# design.net
KiCad netlist of a schematic drawn in EasyEDA Pro
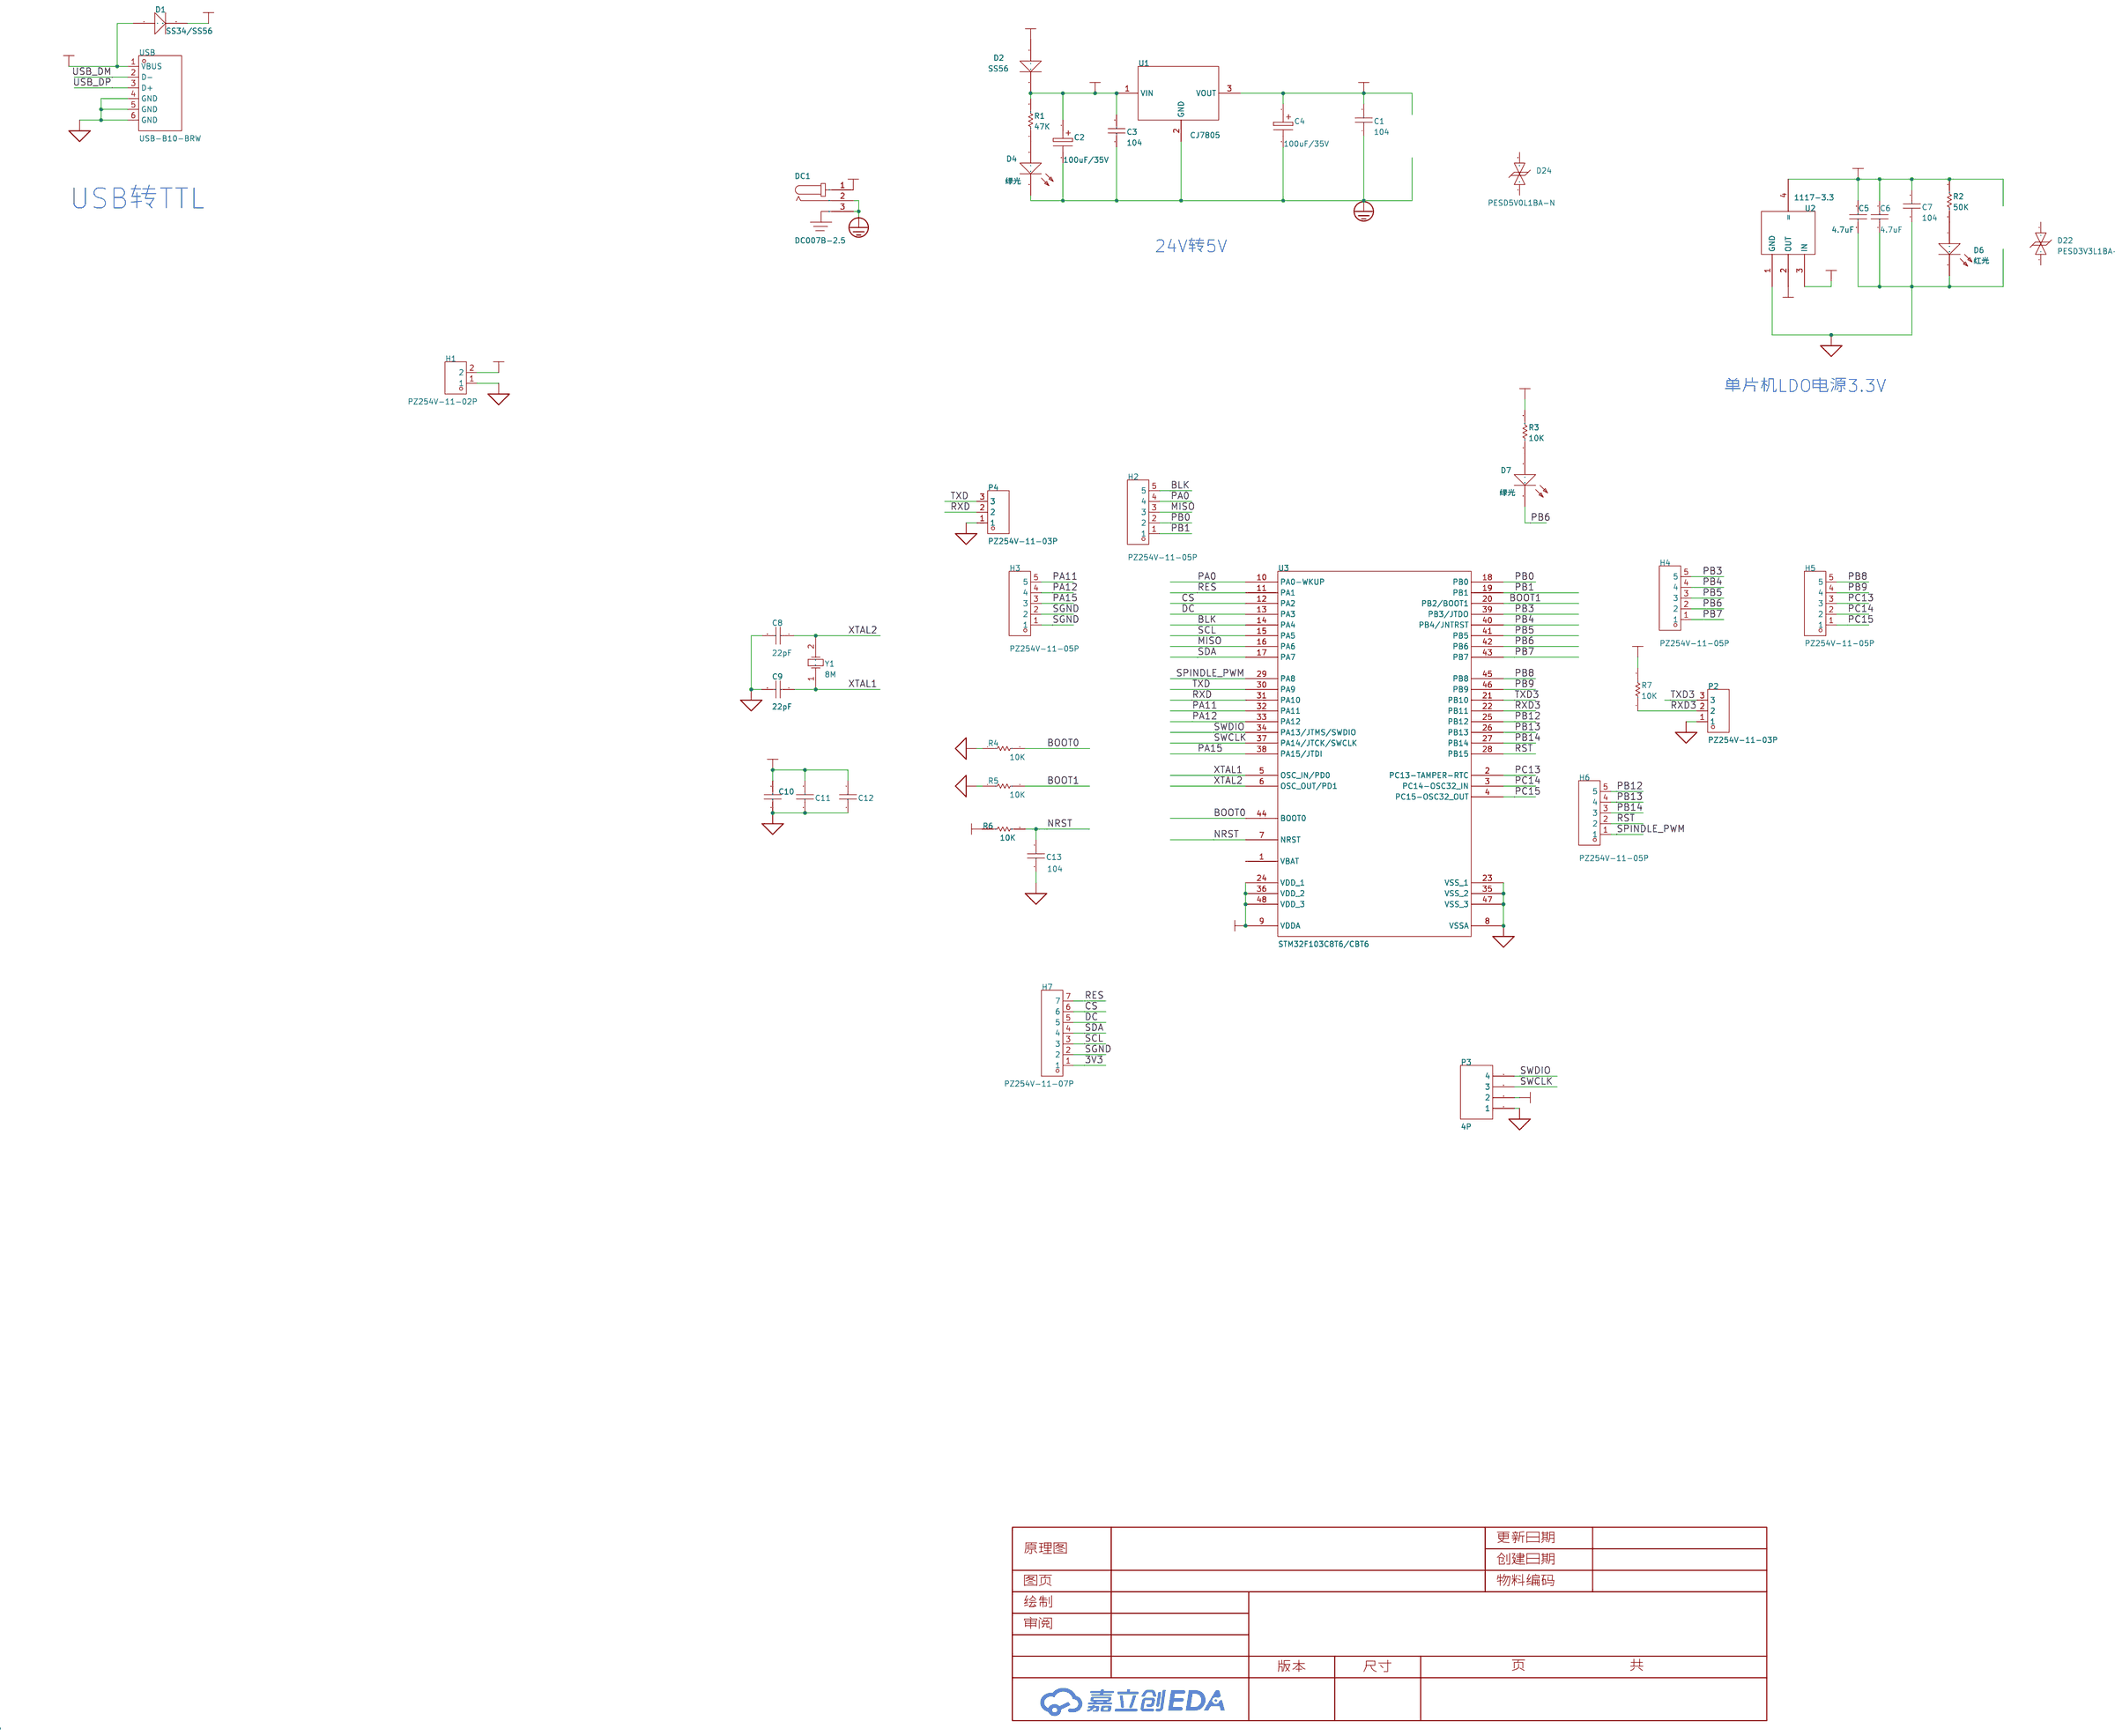
[diagram p0: 主控MCU]
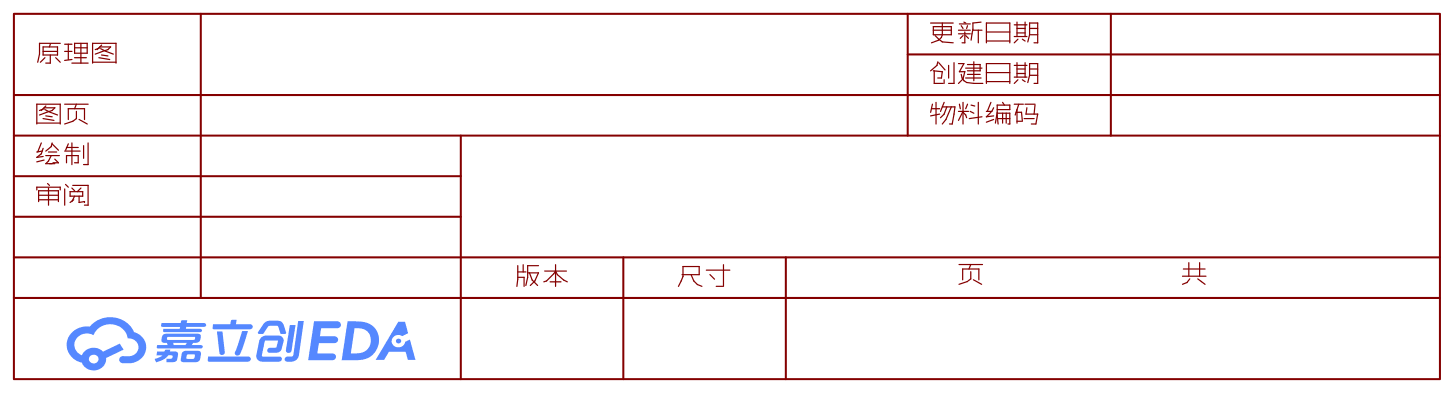
[diagram p1: 电源及控制]

(export (version "E")
  (design (tool "Eeschema 10.0.6"))
  (components
    (comp (ref "C1")
      (value "104")
      (footprint "easyedapro:0603C")
      (description "Capacitor (Semiconductor SIM Model)")
      (libsource (lib "easyedapro") (part "Cap Semi"))
    )
    (comp (ref "C2")
      (value "100uF/35V")
      (footprint "easyedapro:0603C")
      (libsource (lib "easyedapro") (part "ELECTRO1"))
    )
    (comp (ref "C3")
      (value "104")
      (footprint "easyedapro:0603C")
      (description "Capacitor (Semiconductor SIM Model)")
      (libsource (lib "easyedapro") (part "Cap Semi"))
    )
    (comp (ref "C4")
      (value "100uF/35V")
      (footprint "easyedapro:0603C")
      (libsource (lib "easyedapro") (part "ELECTRO1"))
    )
    (comp (ref "C5") (value "4.7uF") (libsource (lib "") (part "CAP_1")))
    (comp (ref "C6") (value "4.7uF") (libsource (lib "") (part "CAP_1")))
    (comp (ref "C7")
      (value "104")
      (footprint "easyedapro:0603C")
      (description "Capacitor (Semiconductor SIM Model)")
      (libsource (lib "easyedapro") (part "Cap Semi"))
    )
    (comp (ref "C8")
      (value "100pF")
      (footprint "easyedapro:0603C")
      (description "Capacitor (Semiconductor SIM Model)")
      (libsource (lib "easyedapro") (part "Cap Semi"))
    )
    (comp (ref "C9")
      (value "100pF")
      (footprint "easyedapro:0603C")
      (description "Capacitor (Semiconductor SIM Model)")
      (libsource (lib "easyedapro") (part "Cap Semi"))
    )
    (comp (ref "C10")
      (value "104")
      (footprint "easyedapro:电解电容贴片6X6")
      (libsource (lib "easyedapro") (part "CAP"))
    )
    (comp (ref "C11")
      (value "104")
      (footprint "easyedapro:电解电容贴片6X6")
      (libsource (lib "easyedapro") (part "CAP"))
    )
    (comp (ref "C12")
      (value "104")
      (footprint "easyedapro:电解电容贴片6X6")
      (libsource (lib "easyedapro") (part "CAP"))
    )
    (comp (ref "C13")
      (value "104")
      (footprint "easyedapro:0603C")
      (description "Capacitor (Semiconductor SIM Model)")
      (libsource (lib "easyedapro") (part "Cap Semi"))
    )
    (comp (ref "D1")
      (value "SS34/SS56")
      (footprint "easyedapro:SMA")
      (libsource (lib "easyedapro") (part "1N4148"))
    )
    (comp (ref "D2")
      (value "SS56")
      (footprint "easyedapro:SMA")
      (libsource (lib "easyedapro") (part "1N4148"))
    )
    (comp (ref "D4")
      (value "绿光")
      (footprint "easyedapro:0603LED")
      (libsource (lib "easyedapro") (part "LED"))
    )
    (comp (ref "D6")
      (value "红光")
      (footprint "easyedapro:0603LED")
      (libsource (lib "easyedapro") (part "LED"))
    )
    (comp (ref "D7")
      (value "绿光")
      (footprint "easyedapro:0603LED")
      (libsource (lib "easyedapro") (part "LED"))
    )
    (comp (ref "D22")
      (value "PESD3V3L1BA-N")
      (footprint "easyedapro:SOD-523_L1.2-W0.8-LS1.6-BI")
      (description "极性:Bidirectional;反向关断电压（典型值）:5V (Max);击穿电压（最小值）:6V;箝位电压:15V;峰值脉冲电流（10/1000us）:5A (8/20us);")
      (fields (field (name "Manufacturer") "BORN伯恩半导体"))
      (libsource (lib "easyedapro") (part "PESD5V0S1BBN"))
    )
    (comp (ref "D24")
      (value "PESD5V0L1BA-N")
      (footprint "easyedapro:SOD-523_L1.2-W0.8-LS1.6-BI")
      (description "极性:Bidirectional;反向关断电压（典型值）:5V (Max);击穿电压（最小值）:6V;箝位电压:15V;峰值脉冲电流（10/1000us）:5A (8/20us);")
      (fields (field (name "Manufacturer") "BORN伯恩半导体"))
      (libsource (lib "easyedapro") (part "PESD5V0S1BBN"))
    )
    (comp (ref "DC1")
      (value "DC007B-2.5")
      (footprint "easyedapro:DC-IN-TH_HX-DC007B-2.5")
      (description "连接器类型:DC电源插座;安装方式:弯插;触点内径:2.5mm;触点外径:7.7mm;额定电流:5A;额定电压:20V;工作温度:-25°C~+70°C;")
      (fields (field (name "Manufacturer") "SHOU HAN(首韩)"))
      (libsource (lib "easyedapro") (part "DC007B-2.5"))
    )
    (comp (ref "H1")
      (value "PZ254V-11-02P")
      (footprint "easyedapro:HDR-TH_2P-P2.54-V-M")
      (fields (field (name "Manufacturer") "XFCN(兴飞)"))
      (libsource (lib "easyedapro") (part "PZ254V-11-02P"))
    )
    (comp (ref "H2")
      (value "PZ254V-11-05P")
      (footprint "easyedapro:HDR-TH_5P-P2.54-V-M")
      (fields (field (name "Manufacturer") "XFCN(兴飞)"))
      (libsource (lib "easyedapro") (part "PZ254V-11-05P"))
    )
    (comp (ref "H3")
      (value "PZ254V-11-05P")
      (footprint "easyedapro:HDR-TH_5P-P2.54-V-M")
      (fields (field (name "Manufacturer") "XFCN(兴飞)"))
      (libsource (lib "easyedapro") (part "PZ254V-11-05P"))
    )
    (comp (ref "H4")
      (value "PZ254V-11-05P")
      (footprint "easyedapro:HDR-TH_5P-P2.54-V-M")
      (fields (field (name "Manufacturer") "XFCN(兴飞)"))
      (libsource (lib "easyedapro") (part "PZ254V-11-05P"))
    )
    (comp (ref "H5")
      (value "PZ254V-11-05P")
      (footprint "easyedapro:HDR-TH_5P-P2.54-V-M")
      (fields (field (name "Manufacturer") "XFCN(兴飞)"))
      (libsource (lib "easyedapro") (part "PZ254V-11-05P"))
    )
    (comp (ref "H6")
      (value "PZ254V-11-05P")
      (footprint "easyedapro:HDR-TH_5P-P2.54-V-M")
      (fields (field (name "Manufacturer") "XFCN(兴飞)"))
      (libsource (lib "easyedapro") (part "PZ254V-11-05P"))
    )
    (comp (ref "H7")
      (value "PZ254V-11-07P")
      (footprint "easyedapro:HDR-TH_7P-P2.54-V-M")
      (fields (field (name "Manufacturer") "XFCN(兴飞)"))
      (libsource (lib "easyedapro") (part "PZ254V-11-07P"))
    )
    (comp (ref "P2")
      (value "PZ254V-11-03P")
      (footprint "easyedapro:HDR-TH_3P-P2.54-V-M")
      (fields (field (name "Manufacturer") "XFCN(兴飞)"))
      (libsource (lib "easyedapro") (part "PZ254V-11-03P_C2937625"))
    )
    (comp (ref "P3") (value "4P") (libsource (lib "easyedapro") (part "4P")))
    (comp (ref "P4")
      (value "PZ254V-11-03P")
      (footprint "easyedapro:HDR-TH_3P-P2.54-V-M")
      (fields (field (name "Manufacturer") "XFCN(兴飞)"))
      (libsource (lib "easyedapro") (part "PZ254V-11-03P_C2937625"))
    )
    (comp (ref "R1")
      (value "47K")
      (footprint "easyedapro:0603R")
      (description "Resistor")
      (libsource (lib "easyedapro") (part "RES"))
    )
    (comp (ref "R2")
      (value "50K")
      (footprint "easyedapro:0603R")
      (description "Resistor")
      (libsource (lib "easyedapro") (part "RES"))
    )
    (comp (ref "R3")
      (value "10K")
      (footprint "easyedapro:0603R")
      (description "Resistor")
      (libsource (lib "easyedapro") (part "RES"))
    )
    (comp (ref "R4")
      (value "10K")
      (footprint "easyedapro:0603R")
      (description "Resistor")
      (libsource (lib "easyedapro") (part "RES"))
    )
    (comp (ref "R5")
      (value "10K")
      (footprint "easyedapro:0603R")
      (description "Resistor")
      (libsource (lib "easyedapro") (part "RES"))
    )
    (comp (ref "R6")
      (value "10K")
      (footprint "easyedapro:0603R")
      (description "Resistor")
      (libsource (lib "easyedapro") (part "RES"))
    )
    (comp (ref "R7")
      (value "10K")
      (footprint "easyedapro:0603R")
      (description "Resistor")
      (libsource (lib "easyedapro") (part "RES"))
    )
    (comp (ref "U1")
      (value "CJ7805")
      (footprint "easyedapro:TO-263-2")
      (libsource (lib "easyedapro") (part "7805"))
    )
    (comp (ref "U2")
      (value "1117-3.3")
      (footprint "easyedapro:SOT-223")
      (libsource (lib "easyedapro") (part "LM1117"))
    )
    (comp (ref "U3")
      (value "STM32F103C8T6/CBT6")
      (footprint "easyedapro:LQFP48")
      (description "STM32 ARM-based 32-bit MCU with 32 Kbytes Flash, 48-pin LQFP, Industrial Temperature")
      (libsource (lib "easyedapro") (part "STM32F103C6T6"))
    )
    (comp (ref "USB")
      (value "USB-B10-BRW")
      (footprint "easyedapro:USB-B-TH_USB-B10-BRW")
      (fields (field (name "Manufacturer") "XUNPU(讯普)"))
      (libsource (lib "easyedapro") (part "USB-B10-BRW"))
    )
    (comp (ref "Y1")
      (value "8M")
      (footprint "easyedapro:晶振贴片49SSMD")
      (description "Crystal Oscillator")
      (libsource (lib "easyedapro") (part "XTAL"))
    )
  )
  (nets
    (net (code "1") (name "3V3") (class "Default")
      (node (ref "C10") (pin "2") (pinfunction "2_2") (pintype "unspecified"))
      (node (ref "C11") (pin "2") (pinfunction "2_2") (pintype "unspecified"))
      (node (ref "C12") (pin "2") (pinfunction "2_2") (pintype "unspecified"))
      (node (ref "C5") (pin "2") (pinfunction "2_2") (pintype "input"))
      (node (ref "C6") (pin "2") (pinfunction "2_2") (pintype "input"))
      (node (ref "C7") (pin "2") (pinfunction "2_2") (pintype "unspecified"))
      (node (ref "H7") (pin "1") (pinfunction "1_1") (pintype "unspecified"))
      (node (ref "P3") (pin "2") (pinfunction "2_2") (pintype "input"))
      (node (ref "R2") (pin "1") (pinfunction "1_1") (pintype "unspecified"))
      (node (ref "R3") (pin "2") (pinfunction "2_2") (pintype "unspecified"))
      (node (ref "R6") (pin "1") (pinfunction "1_1") (pintype "unspecified"))
      (node (ref "R7") (pin "2") (pinfunction "2_2") (pintype "unspecified"))
      (node (ref "U2") (pin "2") (pinfunction "OUT_2") (pintype "unspecified"))
      (node (ref "U2") (pin "4") (pinfunction "=_4") (pintype "unspecified"))
      (node (ref "U3") (pin "24") (pinfunction "VDD_1_24") (pintype "unspecified"))
      (node (ref "U3") (pin "36") (pinfunction "VDD_2_36") (pintype "unspecified"))
      (node (ref "U3") (pin "48") (pinfunction "VDD_3_48") (pintype "unspecified"))
      (node (ref "U3") (pin "9") (pinfunction "VDDA_9") (pintype "unspecified"))
    )
    (net (code "2") (name "5V_VCC") (class "Default")
      (node (ref "C1") (pin "2") (pinfunction "2_2") (pintype "unspecified"))
      (node (ref "C4") (pin "1") (pintype "unspecified"))
      (node (ref "D1") (pin "2") (pinfunction "2_2") (pintype "unspecified"))
      (node (ref "H1") (pin "2") (pinfunction "2_2") (pintype "unspecified"))
      (node (ref "U1") (pin "3") (pinfunction "VOUT_3") (pintype "unspecified"))
      (node (ref "U2") (pin "3") (pinfunction "IN_3") (pintype "unspecified"))
    )
    (net (code "3") (name "24V") (class "Default")
      (node (ref "D2") (pin "1") (pinfunction "1_1") (pintype "unspecified"))
      (node (ref "DC1") (pin "1") (pinfunction "1_1") (pintype "unspecified"))
    )
    (net (code "4") (name "BLK") (class "Default")
      (node (ref "H2") (pin "5") (pinfunction "5_5") (pintype "input"))
      (node (ref "U3") (pin "14") (pinfunction "PA4_14") (pintype "bidirectional"))
    )
    (net (code "5") (name "BOOT0") (class "Default")
      (node (ref "R4") (pin "2") (pinfunction "2_2") (pintype "unspecified"))
      (node (ref "U3") (pin "44") (pinfunction "BOOT0_44") (pintype "input"))
    )
    (net (code "6") (name "BOOT1") (class "Default")
      (node (ref "R5") (pin "2") (pinfunction "2_2") (pintype "unspecified"))
      (node (ref "U3") (pin "20") (pinfunction "PB2/BOOT1_20") (pintype "bidirectional"))
    )
    (net (code "7") (name "CS") (class "Default")
      (node (ref "H7") (pin "6") (pinfunction "6_6") (pintype "unspecified"))
      (node (ref "U3") (pin "12") (pinfunction "PA2_12") (pintype "bidirectional"))
    )
    (net (code "8") (name "DC") (class "Default")
      (node (ref "H7") (pin "5") (pinfunction "5_5") (pintype "unspecified"))
      (node (ref "U3") (pin "13") (pinfunction "PA3_13") (pintype "bidirectional"))
    )
    (net (code "9") (name "MISO") (class "Default")
      (node (ref "H2") (pin "3") (pinfunction "3_3") (pintype "input"))
      (node (ref "U3") (pin "16") (pinfunction "PA6_16") (pintype "bidirectional"))
    )
    (net (code "10") (name "NRST") (class "Default")
      (node (ref "C13") (pin "2") (pinfunction "2_2") (pintype "unspecified"))
      (node (ref "R6") (pin "2") (pinfunction "2_2") (pintype "unspecified"))
      (node (ref "U3") (pin "7") (pinfunction "NRST_7") (pintype "bidirectional"))
    )
    (net (code "11") (name "Net-(D4-Pad1)") (class "Default")
      (node (ref "D4") (pin "1") (pinfunction "1_1") (pintype "unspecified"))
      (node (ref "R1") (pin "1") (pinfunction "1_1") (pintype "unspecified"))
    )
    (net (code "12") (name "Net-(D6-Pad1)") (class "Default")
      (node (ref "D6") (pin "1") (pinfunction "1_1") (pintype "unspecified"))
      (node (ref "R2") (pin "2") (pinfunction "2_2") (pintype "unspecified"))
    )
    (net (code "13") (name "Net-(D7-Pad1)") (class "Default")
      (node (ref "D7") (pin "1") (pinfunction "1_1") (pintype "unspecified"))
      (node (ref "R3") (pin "1") (pinfunction "1_1") (pintype "unspecified"))
    )
    (net (code "14") (name "PA0") (class "Default")
      (node (ref "H2") (pin "4") (pinfunction "4_4") (pintype "input"))
      (node (ref "U3") (pin "10") (pinfunction "PA0-WKUP_10") (pintype "bidirectional"))
    )
    (net (code "15") (name "PA11") (class "Default")
      (node (ref "H3") (pin "5") (pinfunction "5_5") (pintype "input"))
      (node (ref "U3") (pin "32") (pinfunction "PA11_32") (pintype "bidirectional"))
    )
    (net (code "16") (name "PA12") (class "Default")
      (node (ref "H3") (pin "4") (pinfunction "4_4") (pintype "input"))
      (node (ref "U3") (pin "33") (pinfunction "PA12_33") (pintype "bidirectional"))
    )
    (net (code "17") (name "PA15") (class "Default")
      (node (ref "H3") (pin "3") (pinfunction "3_3") (pintype "input"))
      (node (ref "U3") (pin "38") (pinfunction "PA15/JTDI_38") (pintype "bidirectional"))
    )
    (net (code "18") (name "PB0") (class "Default")
      (node (ref "H2") (pin "2") (pinfunction "2_2") (pintype "input"))
      (node (ref "U3") (pin "18") (pinfunction "PB0_18") (pintype "bidirectional"))
    )
    (net (code "19") (name "PB1") (class "Default")
      (node (ref "H2") (pin "1") (pinfunction "1_1") (pintype "input"))
      (node (ref "U3") (pin "19") (pinfunction "PB1_19") (pintype "bidirectional"))
    )
    (net (code "20") (name "PB3") (class "Default")
      (node (ref "H4") (pin "5") (pinfunction "5_5") (pintype "input"))
      (node (ref "U3") (pin "39") (pinfunction "PB3/JTDO_39") (pintype "bidirectional"))
    )
    (net (code "21") (name "PB4") (class "Default")
      (node (ref "H4") (pin "4") (pinfunction "4_4") (pintype "input"))
      (node (ref "U3") (pin "40") (pinfunction "PB4/JNTRST_40") (pintype "bidirectional"))
    )
    (net (code "22") (name "PB5") (class "Default")
      (node (ref "H4") (pin "3") (pinfunction "3_3") (pintype "input"))
      (node (ref "U3") (pin "41") (pinfunction "PB5_41") (pintype "bidirectional"))
    )
    (net (code "23") (name "PB6") (class "Default")
      (node (ref "D7") (pin "2") (pinfunction "2_2") (pintype "unspecified"))
      (node (ref "H4") (pin "2") (pinfunction "2_2") (pintype "input"))
      (node (ref "U3") (pin "42") (pinfunction "PB6_42") (pintype "bidirectional"))
    )
    (net (code "24") (name "PB7") (class "Default")
      (node (ref "H4") (pin "1") (pinfunction "1_1") (pintype "input"))
      (node (ref "U3") (pin "43") (pinfunction "PB7_43") (pintype "bidirectional"))
    )
    (net (code "25") (name "PB8") (class "Default")
      (node (ref "H5") (pin "5") (pinfunction "5_5") (pintype "input"))
      (node (ref "U3") (pin "45") (pinfunction "PB8_45") (pintype "bidirectional"))
    )
    (net (code "26") (name "PB9") (class "Default")
      (node (ref "H5") (pin "4") (pinfunction "4_4") (pintype "input"))
      (node (ref "U3") (pin "46") (pinfunction "PB9_46") (pintype "bidirectional"))
    )
    (net (code "27") (name "PB12") (class "Default")
      (node (ref "H6") (pin "5") (pinfunction "5_5") (pintype "input"))
      (node (ref "U3") (pin "25") (pinfunction "PB12_25") (pintype "bidirectional"))
    )
    (net (code "28") (name "PB13") (class "Default")
      (node (ref "H6") (pin "4") (pinfunction "4_4") (pintype "input"))
      (node (ref "U3") (pin "26") (pinfunction "PB13_26") (pintype "bidirectional"))
    )
    (net (code "29") (name "PB14") (class "Default")
      (node (ref "H6") (pin "3") (pinfunction "3_3") (pintype "input"))
      (node (ref "U3") (pin "27") (pinfunction "PB14_27") (pintype "bidirectional"))
    )
    (net (code "30") (name "PC13") (class "Default")
      (node (ref "H5") (pin "3") (pinfunction "3_3") (pintype "input"))
      (node (ref "U3") (pin "2") (pinfunction "PC13-TAMPER-RTC_2") (pintype "bidirectional"))
    )
    (net (code "31") (name "PC14") (class "Default")
      (node (ref "H5") (pin "2") (pinfunction "2_2") (pintype "input"))
      (node (ref "U3") (pin "3") (pinfunction "PC14-OSC32_IN_3") (pintype "bidirectional"))
    )
    (net (code "32") (name "PC15") (class "Default")
      (node (ref "H5") (pin "1") (pinfunction "1_1") (pintype "input"))
      (node (ref "U3") (pin "4") (pinfunction "PC15-OSC32_OUT_4") (pintype "bidirectional"))
    )
    (net (code "33") (name "RES") (class "Default")
      (node (ref "H7") (pin "7") (pinfunction "7_7") (pintype "unspecified"))
      (node (ref "U3") (pin "11") (pinfunction "PA1_11") (pintype "bidirectional"))
    )
    (net (code "34") (name "RST") (class "Default")
      (node (ref "H6") (pin "2") (pinfunction "2_2") (pintype "input"))
      (node (ref "U3") (pin "28") (pinfunction "PB15_28") (pintype "bidirectional"))
    )
    (net (code "35") (name "RXD") (class "Default")
      (node (ref "P4") (pin "2") (pinfunction "2_2") (pintype "unspecified"))
      (node (ref "U3") (pin "31") (pinfunction "PA10_31") (pintype "bidirectional"))
    )
    (net (code "36") (name "RXD3") (class "Default")
      (node (ref "P2") (pin "2") (pinfunction "2_2") (pintype "unspecified"))
      (node (ref "R7") (pin "1") (pinfunction "1_1") (pintype "unspecified"))
      (node (ref "U3") (pin "22") (pinfunction "PB11_22") (pintype "bidirectional"))
    )
    (net (code "37") (name "SCL") (class "Default")
      (node (ref "H7") (pin "3") (pinfunction "3_3") (pintype "unspecified"))
      (node (ref "U3") (pin "15") (pinfunction "PA5_15") (pintype "bidirectional"))
    )
    (net (code "38") (name "SDA") (class "Default")
      (node (ref "H7") (pin "4") (pinfunction "4_4") (pintype "unspecified"))
      (node (ref "U3") (pin "17") (pinfunction "PA7_17") (pintype "bidirectional"))
    )
    (net (code "39") (name "SGND") (class "Default")
      (node (ref "C1") (pin "1") (pinfunction "1_1") (pintype "unspecified"))
      (node (ref "C10") (pin "1") (pinfunction "1_1") (pintype "unspecified"))
      (node (ref "C11") (pin "1") (pinfunction "1_1") (pintype "unspecified"))
      (node (ref "C12") (pin "1") (pinfunction "1_1") (pintype "unspecified"))
      (node (ref "C13") (pin "1") (pinfunction "1_1") (pintype "unspecified"))
      (node (ref "C2") (pin "2") (pintype "unspecified"))
      (node (ref "C3") (pin "1") (pinfunction "1_1") (pintype "unspecified"))
      (node (ref "C4") (pin "2") (pintype "unspecified"))
      (node (ref "C5") (pin "1") (pinfunction "1_1") (pintype "input"))
      (node (ref "C6") (pin "1") (pinfunction "1_1") (pintype "input"))
      (node (ref "C7") (pin "1") (pinfunction "1_1") (pintype "unspecified"))
      (node (ref "C8") (pin "2") (pinfunction "2_2") (pintype "unspecified"))
      (node (ref "C9") (pin "2") (pinfunction "2_2") (pintype "unspecified"))
      (node (ref "D4") (pin "2") (pinfunction "2_2") (pintype "unspecified"))
      (node (ref "D6") (pin "2") (pinfunction "2_2") (pintype "unspecified"))
      (node (ref "DC1") (pin "2") (pinfunction "2_2") (pintype "unspecified"))
      (node (ref "DC1") (pin "3") (pinfunction "3_3") (pintype "unspecified"))
      (node (ref "H1") (pin "1") (pinfunction "1_1") (pintype "unspecified"))
      (node (ref "H3") (pin "1") (pinfunction "1_1") (pintype "input"))
      (node (ref "H3") (pin "2") (pinfunction "2_2") (pintype "input"))
      (node (ref "H7") (pin "2") (pinfunction "2_2") (pintype "unspecified"))
      (node (ref "P2") (pin "1") (pinfunction "1_1") (pintype "unspecified"))
      (node (ref "P3") (pin "1") (pinfunction "1_1") (pintype "input"))
      (node (ref "P4") (pin "1") (pinfunction "1_1") (pintype "unspecified"))
      (node (ref "R4") (pin "1") (pinfunction "1_1") (pintype "unspecified"))
      (node (ref "R5") (pin "1") (pinfunction "1_1") (pintype "unspecified"))
      (node (ref "U1") (pin "2") (pinfunction "GND_2") (pintype "unspecified"))
      (node (ref "U2") (pin "1") (pinfunction "GND_1") (pintype "unspecified"))
      (node (ref "U3") (pin "23") (pinfunction "VSS_1_23") (pintype "unspecified"))
      (node (ref "U3") (pin "35") (pinfunction "VSS_2_35") (pintype "unspecified"))
      (node (ref "U3") (pin "47") (pinfunction "VSS_3_47") (pintype "unspecified"))
      (node (ref "U3") (pin "8") (pinfunction "VSSA_8") (pintype "unspecified"))
      (node (ref "USB") (pin "4") (pinfunction "GND_4") (pintype "unspecified"))
      (node (ref "USB") (pin "5") (pinfunction "GND_5") (pintype "unspecified"))
      (node (ref "USB") (pin "6") (pinfunction "GND_6") (pintype "unspecified"))
    )
    (net (code "40") (name "SPINDLE_PWM") (class "Default")
      (node (ref "H6") (pin "1") (pinfunction "1_1") (pintype "input"))
      (node (ref "U3") (pin "29") (pinfunction "PA8_29") (pintype "bidirectional"))
    )
    (net (code "41") (name "SWCLK") (class "Default")
      (node (ref "P3") (pin "3") (pinfunction "3_3") (pintype "input"))
      (node (ref "U3") (pin "37") (pinfunction "PA14/JTCK/SWCLK_37") (pintype "bidirectional"))
    )
    (net (code "42") (name "SWDIO") (class "Default")
      (node (ref "P3") (pin "4") (pinfunction "4_4") (pintype "input"))
      (node (ref "U3") (pin "34") (pinfunction "PA13/JTMS/SWDIO_34") (pintype "bidirectional"))
    )
    (net (code "43") (name "TXD") (class "Default")
      (node (ref "P4") (pin "3") (pinfunction "3_3") (pintype "unspecified"))
      (node (ref "U3") (pin "30") (pinfunction "PA9_30") (pintype "bidirectional"))
    )
    (net (code "44") (name "TXD3") (class "Default")
      (node (ref "P2") (pin "3") (pinfunction "3_3") (pintype "unspecified"))
      (node (ref "U3") (pin "21") (pinfunction "PB10_21") (pintype "bidirectional"))
    )
    (net (code "45") (name "USB_DM") (class "Default")
      (node (ref "USB") (pin "2") (pinfunction "D-_2") (pintype "unspecified"))
    )
    (net (code "46") (name "USB_DP") (class "Default")
      (node (ref "USB") (pin "3") (pinfunction "D+_3") (pintype "unspecified"))
    )
    (net (code "47") (name "VIN_24V") (class "Default")
      (node (ref "C2") (pin "1") (pintype "unspecified"))
      (node (ref "C3") (pin "2") (pinfunction "2_2") (pintype "unspecified"))
      (node (ref "D2") (pin "2") (pinfunction "2_2") (pintype "unspecified"))
      (node (ref "R1") (pin "2") (pinfunction "2_2") (pintype "unspecified"))
      (node (ref "U1") (pin "1") (pinfunction "VIN_1") (pintype "unspecified"))
    )
    (net (code "48") (name "VUSB") (class "Default")
      (node (ref "D1") (pin "1") (pinfunction "1_1") (pintype "unspecified"))
      (node (ref "USB") (pin "1") (pinfunction "VBUS_1") (pintype "unspecified"))
    )
    (net (code "49") (name "XTAL1") (class "Default")
      (node (ref "C9") (pin "1") (pinfunction "1_1") (pintype "unspecified"))
      (node (ref "U3") (pin "5") (pinfunction "OSC_IN/PD0_5") (pintype "input"))
      (node (ref "Y1") (pin "1") (pinfunction "OSC1_1") (pintype "unspecified"))
    )
    (net (code "50") (name "XTAL2") (class "Default")
      (node (ref "C8") (pin "1") (pinfunction "1_1") (pintype "unspecified"))
      (node (ref "U3") (pin "6") (pinfunction "OSC_OUT/PD1_6") (pintype "output"))
      (node (ref "Y1") (pin "2") (pinfunction "OSC2_2") (pintype "unspecified"))
    )
    (net (code "51") (name "unconnected-(D22-Pad1)") (class "Default")
      (node (ref "D22") (pin "1") (pinfunction "1_1") (pintype "input"))
    )
    (net (code "52") (name "unconnected-(D22-Pad2)") (class "Default")
      (node (ref "D22") (pin "2") (pinfunction "2_2") (pintype "input"))
    )
    (net (code "53") (name "unconnected-(D24-Pad1)") (class "Default")
      (node (ref "D24") (pin "1") (pinfunction "1_1") (pintype "input"))
    )
    (net (code "54") (name "unconnected-(D24-Pad2)") (class "Default")
      (node (ref "D24") (pin "2") (pinfunction "2_2") (pintype "input"))
    )
    (net (code "55") (name "unconnected-(U3-VBAT-Pad1)") (class "Default")
      (node (ref "U3") (pin "1") (pinfunction "VBAT_1") (pintype "unspecified"))
    )
  )
)
